# OttoPi09-RPi3A-HAT.net
KiCad netlist of a schematic drawn in EAGLE
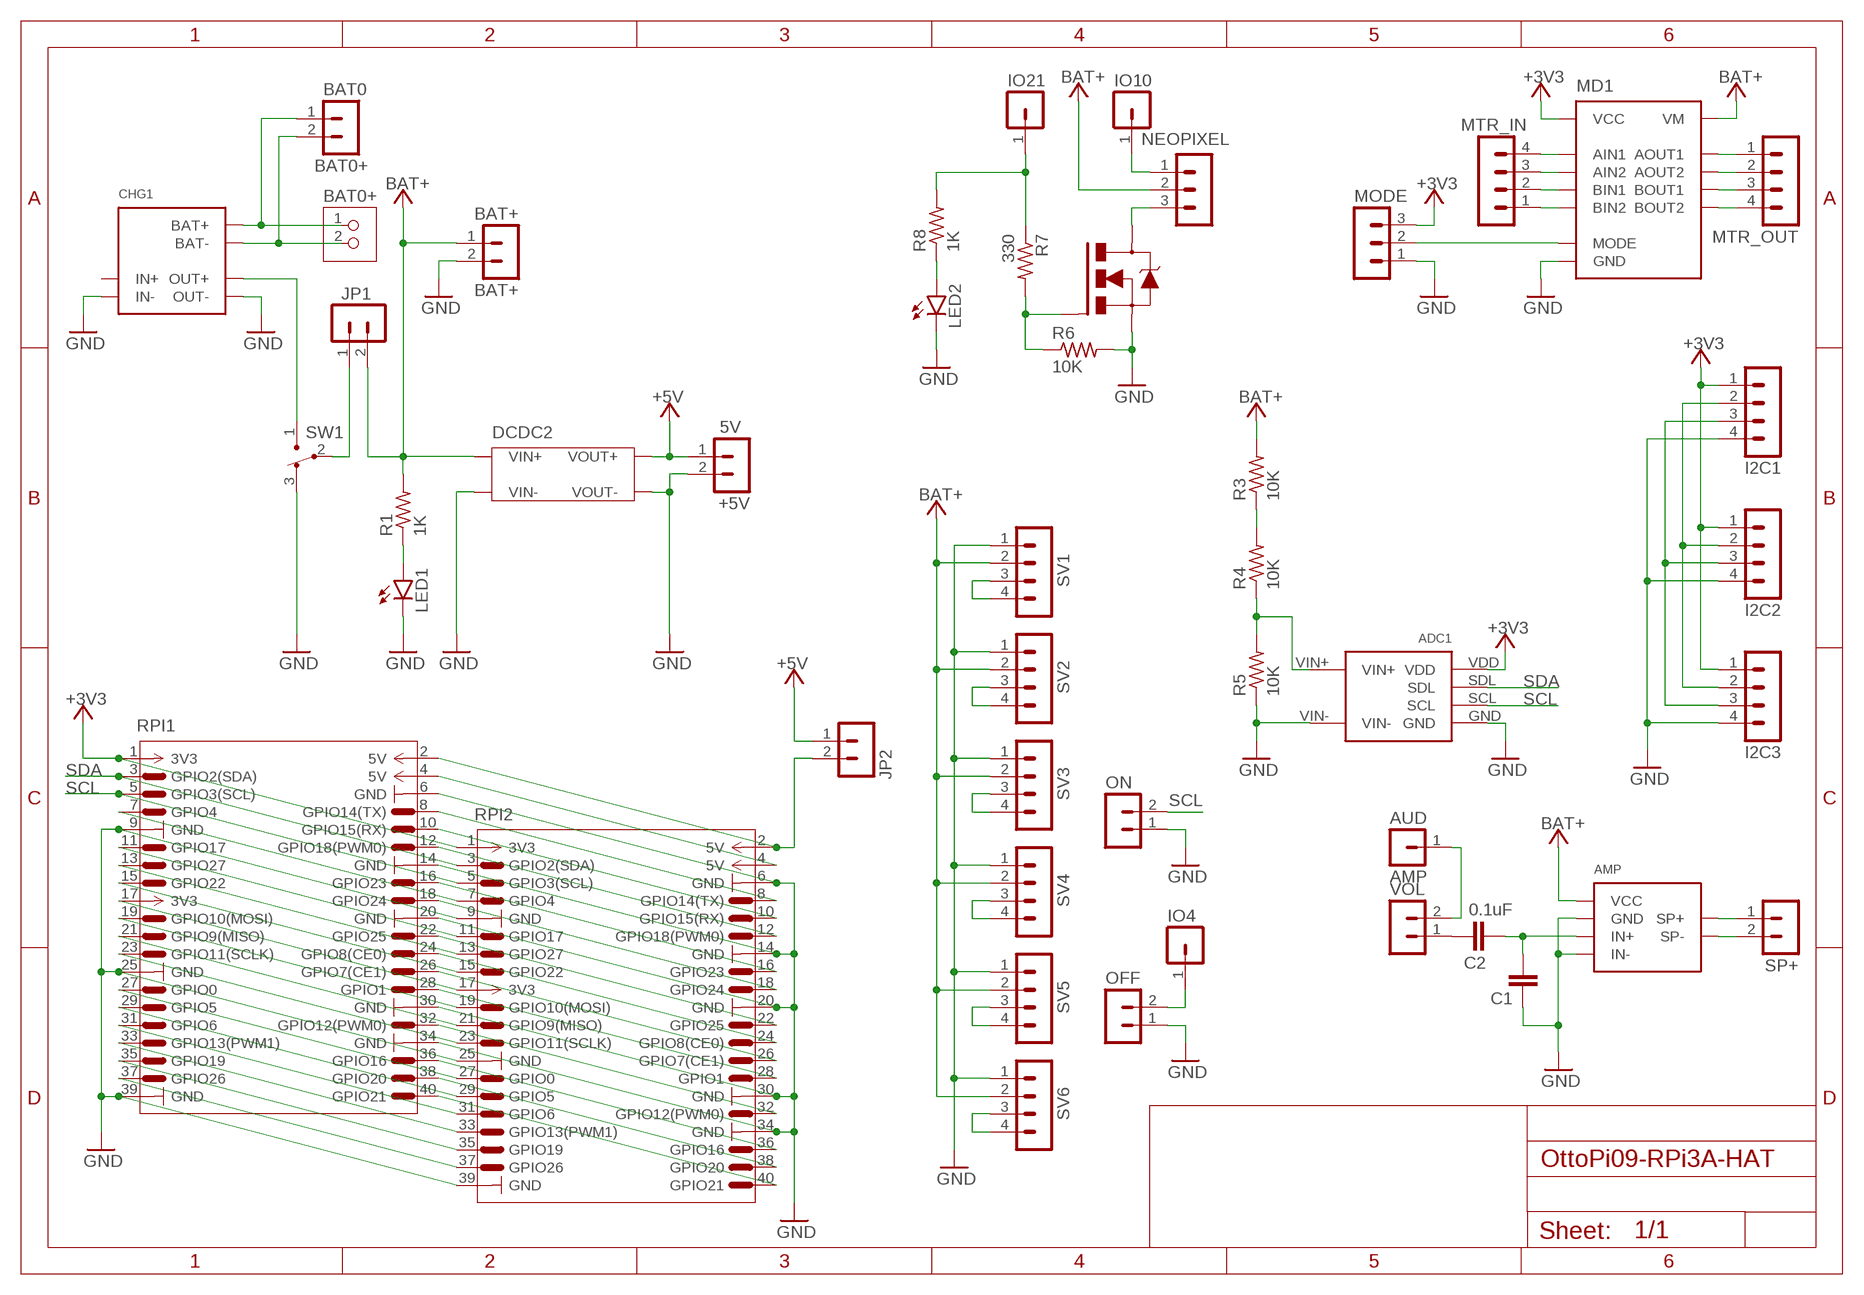
[diagram p0: schematic, sheet 1]

(export (version "E")
  (design (tool "Eeschema 10.0.6"))
  (components
    (comp (ref "+5V")
      (value "5V")
      (footprint "eagle-import:PINHEAD-MA02-1")
      (libsource (lib "eagle-import") (part "PINHEAD-MA02-1"))
    )
    (comp (ref "ADC1")
      (value "MCP3425MOD")
      (footprint "eagle-import:MCP3425MOD")
      (libsource (lib "eagle-import") (part "MCP3425MOD"))
    )
    (comp (ref "AMP")
      (value "AMP")
      (footprint "eagle-import:PAM8012MOD-A")
      (libsource (lib "eagle-import") (part "PAM8012MOD"))
    )
    (comp (ref "AUD")
      (value "AMP")
      (footprint "eagle-import:PINHEAD-MA01-1")
      (libsource (lib "eagle-import") (part "PINHEAD-MA01-1"))
    )
    (comp (ref "BAT+")
      (value "BAT+")
      (footprint "eagle-import:PINHEAD-MA02-1")
      (libsource (lib "eagle-import") (part "PINHEAD-MA02-1"))
    )
    (comp (ref "BAT0")
      (value "BAT0+")
      (footprint "eagle-import:PINHEAD-MA02-1")
      (libsource (lib "eagle-import") (part "PINHEAD-MA02-1"))
    )
    (comp (ref "BAT0+")
      (value "JST-PH2")
      (footprint "eagle-import:JST-PH2")
      (libsource (lib "eagle-import") (part "JST-PH2"))
    )
    (comp (ref "C1")
      (value "C-EU025-024X044")
      (footprint "eagle-import:C025-024X044")
      (libsource (lib "eagle-import") (part "C-EU025-024X044"))
    )
    (comp (ref "C2")
      (value "0.1uF")
      (footprint "eagle-import:C025-024X044")
      (libsource (lib "eagle-import") (part "C-EU025-024X044"))
    )
    (comp (ref "CHG1")
      (value "TP4056MOD1")
      (footprint "eagle-import:TP4056MOD1")
      (libsource (lib "eagle-import") (part "TP4056MOD1"))
    )
    (comp (ref "DCDC2")
      (value "DCDC-SX1308-MOD1")
      (footprint "eagle-import:DCDC-SX1308-MOD1")
      (libsource (lib "eagle-import") (part "DCDC-SX1308-MOD1"))
    )
    (comp (ref "I2C1")
      (value "PINHEAD-MA04-1")
      (footprint "eagle-import:PINHEAD-MA04-1")
      (libsource (lib "eagle-import") (part "PINHEAD-MA04-1"))
    )
    (comp (ref "I2C2")
      (value "PINHEAD-MA04-1")
      (footprint "eagle-import:PINHEAD-MA04-1")
      (libsource (lib "eagle-import") (part "PINHEAD-MA04-1"))
    )
    (comp (ref "I2C3")
      (value "PINHEAD-MA04-1")
      (footprint "eagle-import:PINHEAD-MA04-1")
      (libsource (lib "eagle-import") (part "PINHEAD-MA04-1"))
    )
    (comp (ref "IO4")
      (value "PINHEAD-MA01-1")
      (footprint "eagle-import:PINHEAD-MA01-1")
      (libsource (lib "eagle-import") (part "PINHEAD-MA01-1"))
    )
    (comp (ref "IO10")
      (value "PINHEAD-MA01-1")
      (footprint "eagle-import:PINHEAD-MA01-1")
      (libsource (lib "eagle-import") (part "PINHEAD-MA01-1"))
    )
    (comp (ref "IO21")
      (value "PINHEAD-MA01-1")
      (footprint "eagle-import:PINHEAD-MA01-1")
      (libsource (lib "eagle-import") (part "PINHEAD-MA01-1"))
    )
    (comp (ref "JP1")
      (value "PINHEAD-MA02-1")
      (footprint "eagle-import:PINHEAD-MA02-1")
      (libsource (lib "eagle-import") (part "PINHEAD-MA02-1"))
    )
    (comp (ref "JP2")
      (value "PINHEAD-MA02-1")
      (footprint "eagle-import:PINHEAD-MA02-1")
      (libsource (lib "eagle-import") (part "PINHEAD-MA02-1"))
    )
    (comp (ref "LED1")
      (value "LED3MM")
      (footprint "eagle-import:LED3MM")
      (libsource (lib "eagle-import") (part "LED3MM"))
    )
    (comp (ref "LED2")
      (value "LED3MM")
      (footprint "eagle-import:LED3MM")
      (libsource (lib "eagle-import") (part "LED3MM"))
    )
    (comp (ref "MD1")
      (value "DRV8835MOD")
      (footprint "eagle-import:DRV8835MOD")
      (libsource (lib "eagle-import") (part "DRV8835MOD"))
    )
    (comp (ref "MODE")
      (value "PINHEAD-MA03-1")
      (footprint "eagle-import:PINHEAD-MA03-1")
      (libsource (lib "eagle-import") (part "PINHEAD-MA03-1"))
    )
    (comp (ref "MTR_IN")
      (value "PINHEAD-MA04-1")
      (footprint "eagle-import:PINHEAD-MA04-1")
      (libsource (lib "eagle-import") (part "PINHEAD-MA04-1"))
    )
    (comp (ref "MTR_OUT")
      (value "PINHEAD-MA04-1")
      (footprint "eagle-import:PINHEAD-MA04-1")
      (libsource (lib "eagle-import") (part "PINHEAD-MA04-1"))
    )
    (comp (ref "NEOPIXEL")
      (value "PINHEAD-MA03-1")
      (footprint "eagle-import:PINHEAD-MA03-1")
      (libsource (lib "eagle-import") (part "ytani1_30941153_PINHEAD-MA03-1"))
    )
    (comp (ref "OFF")
      (value "PINHEAD-MA02-1")
      (footprint "eagle-import:PINHEAD-MA02-1")
      (libsource (lib "eagle-import") (part "PINHEAD-MA02-1"))
    )
    (comp (ref "ON")
      (value "PINHEAD-MA02-1")
      (footprint "eagle-import:PINHEAD-MA02-1")
      (libsource (lib "eagle-import") (part "PINHEAD-MA02-1"))
    )
    (comp (ref "Q1")
      (value "2SK4017")
      (footprint "eagle-import:MOSFET-1")
      (libsource (lib "eagle-import") (part "MOSFET-2SK4017"))
    )
    (comp (ref "R1")
      (value "1K")
      (footprint "eagle-import:0204_7")
      (libsource (lib "eagle-import") (part "R-US_0204/7"))
    )
    (comp (ref "R3")
      (value "10K")
      (footprint "eagle-import:0204_7")
      (libsource (lib "eagle-import") (part "R-US_0204/7"))
    )
    (comp (ref "R4")
      (value "10K")
      (footprint "eagle-import:0204_7")
      (libsource (lib "eagle-import") (part "R-US_0204/7"))
    )
    (comp (ref "R5")
      (value "10K")
      (footprint "eagle-import:0204_7")
      (libsource (lib "eagle-import") (part "R-US_0204/7"))
    )
    (comp (ref "R6")
      (value "10K")
      (footprint "eagle-import:0204_7")
      (libsource (lib "eagle-import") (part "R-US_0204/7"))
    )
    (comp (ref "R7")
      (value "330")
      (footprint "eagle-import:0204_7")
      (libsource (lib "eagle-import") (part "R-US_0204/7"))
    )
    (comp (ref "R8")
      (value "1K")
      (footprint "eagle-import:0204_7")
      (libsource (lib "eagle-import") (part "R-US_0204/7"))
    )
    (comp (ref "RPI1")
      (value "RPI-PIN")
      (footprint "eagle-import:RPI-PIN")
      (libsource (lib "eagle-import") (part "RPI-PIN"))
    )
    (comp (ref "RPI2")
      (value "RPI-PIN")
      (footprint "eagle-import:RPI-PIN")
      (libsource (lib "eagle-import") (part "RPI-PIN"))
    )
    (comp (ref "SP+")
      (value "PINHEAD-MA02-1")
      (footprint "eagle-import:PINHEAD-MA02-1")
      (libsource (lib "eagle-import") (part "PINHEAD-MA02-1"))
    )
    (comp (ref "SV1")
      (value "PINHEAD-MA04-1")
      (footprint "eagle-import:PINHEAD-MA04-1")
      (libsource (lib "eagle-import") (part "PINHEAD-MA04-1"))
    )
    (comp (ref "SV2")
      (value "PINHEAD-MA04-1")
      (footprint "eagle-import:PINHEAD-MA04-1")
      (libsource (lib "eagle-import") (part "PINHEAD-MA04-1"))
    )
    (comp (ref "SV3")
      (value "PINHEAD-MA04-1")
      (footprint "eagle-import:PINHEAD-MA04-1")
      (libsource (lib "eagle-import") (part "PINHEAD-MA04-1"))
    )
    (comp (ref "SV4")
      (value "PINHEAD-MA04-1")
      (footprint "eagle-import:PINHEAD-MA04-1")
      (libsource (lib "eagle-import") (part "PINHEAD-MA04-1"))
    )
    (comp (ref "SV5")
      (value "PINHEAD-MA04-1")
      (footprint "eagle-import:PINHEAD-MA04-1")
      (libsource (lib "eagle-import") (part "PINHEAD-MA04-1"))
    )
    (comp (ref "SV6")
      (value "PINHEAD-MA04-1")
      (footprint "eagle-import:PINHEAD-MA04-1")
      (libsource (lib "eagle-import") (part "PINHEAD-MA04-1"))
    )
    (comp (ref "SW1")
      (value "SW3-1")
      (footprint "eagle-import:SW3-1")
      (fields (field (name "MF") "HiLetgo"))
      (libsource (lib "eagle-import") (part "SW3-1"))
    )
    (comp (ref "VOL")
      (value "PINHEAD-MA02-1")
      (footprint "eagle-import:PINHEAD-MA02-1")
      (libsource (lib "eagle-import") (part "PINHEAD-MA02-1"))
    )
  )
  (nets
    (net (code "1") (name "+3V3") (class "Default")
      (node (ref "ADC1") (pin "VDD") (pinfunction "VDD_VDD") (pintype "bidirectional"))
      (node (ref "I2C1") (pin "1") (pinfunction "1_1") (pintype "passive"))
      (node (ref "I2C2") (pin "1") (pinfunction "1_1") (pintype "passive"))
      (node (ref "I2C3") (pin "1") (pinfunction "1_1") (pintype "passive"))
      (node (ref "MD1") (pin "VCC") (pinfunction "VCC_VCC") (pintype "input"))
      (node (ref "MODE") (pin "3") (pinfunction "3_3") (pintype "passive"))
      (node (ref "RPI1") (pin "1") (pinfunction "3V3_1") (pintype "passive"))
      (node (ref "RPI2") (pin "1") (pinfunction "3V3_1") (pintype "passive"))
    )
    (net (code "2") (name "+5V") (class "Default")
      (node (ref "+5V") (pin "1") (pinfunction "1_1") (pintype "passive"))
      (node (ref "DCDC2") (pin "VOUT+") (pinfunction "VOUT+_VOUT+") (pintype "power_in"))
      (node (ref "JP2") (pin "1") (pinfunction "1_1") (pintype "passive"))
    )
    (net (code "3") (name "/SCL") (class "Default")
      (node (ref "ADC1") (pin "SCL") (pinfunction "SCL_SCL") (pintype "bidirectional"))
      (node (ref "I2C1") (pin "3") (pinfunction "3_3") (pintype "passive"))
      (node (ref "I2C2") (pin "3") (pinfunction "3_3") (pintype "passive"))
      (node (ref "I2C3") (pin "3") (pinfunction "3_3") (pintype "passive"))
      (node (ref "ON") (pin "2") (pinfunction "2_2") (pintype "passive"))
      (node (ref "RPI1") (pin "5") (pinfunction "GPIO3(SCL)_5") (pintype "passive"))
      (node (ref "RPI2") (pin "5") (pinfunction "GPIO3(SCL)_5") (pintype "passive"))
    )
    (net (code "4") (name "/SDA") (class "Default")
      (node (ref "ADC1") (pin "SDL") (pinfunction "SDL_SDL") (pintype "bidirectional"))
      (node (ref "I2C1") (pin "2") (pinfunction "2_2") (pintype "passive"))
      (node (ref "I2C2") (pin "2") (pinfunction "2_2") (pintype "passive"))
      (node (ref "I2C3") (pin "2") (pinfunction "2_2") (pintype "passive"))
      (node (ref "RPI1") (pin "3") (pinfunction "GPIO2(SDA)_3") (pintype "passive"))
      (node (ref "RPI2") (pin "3") (pinfunction "GPIO2(SDA)_3") (pintype "passive"))
    )
    (net (code "5") (name "BAT+") (class "Default")
      (node (ref "AMP") (pin "V+") (pinfunction "VCC_V+") (pintype "passive"))
      (node (ref "BAT+") (pin "1") (pinfunction "1_1") (pintype "passive"))
      (node (ref "DCDC2") (pin "VIN+") (pinfunction "VIN+_VIN+") (pintype "power_in"))
      (node (ref "JP1") (pin "2") (pinfunction "2_2") (pintype "passive"))
      (node (ref "MD1") (pin "VM") (pinfunction "VM_VM") (pintype "input"))
      (node (ref "NEOPIXEL") (pin "2") (pinfunction "2_2") (pintype "passive"))
      (node (ref "R1") (pin "2") (pinfunction "2_2") (pintype "passive"))
      (node (ref "R3") (pin "2") (pinfunction "2_2") (pintype "passive"))
      (node (ref "SV1") (pin "2") (pinfunction "2_2") (pintype "passive"))
      (node (ref "SV2") (pin "2") (pinfunction "2_2") (pintype "passive"))
      (node (ref "SV3") (pin "2") (pinfunction "2_2") (pintype "passive"))
      (node (ref "SV4") (pin "2") (pinfunction "2_2") (pintype "passive"))
      (node (ref "SV5") (pin "2") (pinfunction "2_2") (pintype "passive"))
      (node (ref "SV6") (pin "2") (pinfunction "2_2") (pintype "passive"))
    )
    (net (code "6") (name "GND") (class "Default")
      (node (ref "+5V") (pin "2") (pinfunction "2_2") (pintype "passive"))
      (node (ref "ADC1") (pin "GND") (pinfunction "GND_GND") (pintype "bidirectional"))
      (node (ref "ADC1") (pin "VIN-") (pinfunction "VIN-_VIN-") (pintype "bidirectional"))
      (node (ref "AMP") (pin "GND") (pinfunction "GND_GND") (pintype "passive"))
      (node (ref "AMP") (pin "IN-") (pinfunction "IN-_IN-") (pintype "input"))
      (node (ref "BAT+") (pin "2") (pinfunction "2_2") (pintype "passive"))
      (node (ref "C1") (pin "1") (pinfunction "1_1") (pintype "passive"))
      (node (ref "CHG1") (pin "IN-") (pinfunction "IN-_IN-") (pintype "passive"))
      (node (ref "CHG1") (pin "OUT-") (pinfunction "OUT-_OUT-") (pintype "passive"))
      (node (ref "DCDC2") (pin "VIN-") (pinfunction "VIN-_VIN-") (pintype "power_in"))
      (node (ref "DCDC2") (pin "VOUT-") (pinfunction "VOUT-_VOUT-") (pintype "power_in"))
      (node (ref "I2C1") (pin "4") (pinfunction "4_4") (pintype "passive"))
      (node (ref "I2C2") (pin "4") (pinfunction "4_4") (pintype "passive"))
      (node (ref "I2C3") (pin "4") (pinfunction "4_4") (pintype "passive"))
      (node (ref "LED1") (pin "K") (pinfunction "C_K") (pintype "passive"))
      (node (ref "LED2") (pin "K") (pinfunction "C_K") (pintype "passive"))
      (node (ref "MD1") (pin "GND") (pinfunction "GND_GND") (pintype "power_in"))
      (node (ref "MODE") (pin "1") (pinfunction "1_1") (pintype "passive"))
      (node (ref "OFF") (pin "1") (pinfunction "1_1") (pintype "passive"))
      (node (ref "ON") (pin "1") (pinfunction "1_1") (pintype "passive"))
      (node (ref "Q1") (pin "S") (pinfunction "S_S") (pintype "bidirectional"))
      (node (ref "R5") (pin "1") (pinfunction "1_1") (pintype "passive"))
      (node (ref "R6") (pin "2") (pinfunction "2_2") (pintype "passive"))
      (node (ref "RPI1") (pin "14") (pinfunction "GND_14") (pintype "passive"))
      (node (ref "RPI1") (pin "20") (pinfunction "GND_20") (pintype "passive"))
      (node (ref "RPI1") (pin "25") (pinfunction "GND_25") (pintype "passive"))
      (node (ref "RPI1") (pin "30") (pinfunction "GND_30") (pintype "passive"))
      (node (ref "RPI1") (pin "34") (pinfunction "GND_34") (pintype "passive"))
      (node (ref "RPI1") (pin "39") (pinfunction "GND_39") (pintype "passive"))
      (node (ref "RPI1") (pin "6") (pinfunction "GND_6") (pintype "passive"))
      (node (ref "RPI1") (pin "9") (pinfunction "GND_9") (pintype "passive"))
      (node (ref "RPI2") (pin "14") (pinfunction "GND_14") (pintype "passive"))
      (node (ref "RPI2") (pin "20") (pinfunction "GND_20") (pintype "passive"))
      (node (ref "RPI2") (pin "25") (pinfunction "GND_25") (pintype "passive"))
      (node (ref "RPI2") (pin "30") (pinfunction "GND_30") (pintype "passive"))
      (node (ref "RPI2") (pin "34") (pinfunction "GND_34") (pintype "passive"))
      (node (ref "RPI2") (pin "39") (pinfunction "GND_39") (pintype "passive"))
      (node (ref "RPI2") (pin "6") (pinfunction "GND_6") (pintype "passive"))
      (node (ref "RPI2") (pin "9") (pinfunction "GND_9") (pintype "passive"))
      (node (ref "SV1") (pin "1") (pinfunction "1_1") (pintype "passive"))
      (node (ref "SV2") (pin "1") (pinfunction "1_1") (pintype "passive"))
      (node (ref "SV3") (pin "1") (pinfunction "1_1") (pintype "passive"))
      (node (ref "SV4") (pin "1") (pinfunction "1_1") (pintype "passive"))
      (node (ref "SV5") (pin "1") (pinfunction "1_1") (pintype "passive"))
      (node (ref "SV6") (pin "1") (pinfunction "1_1") (pintype "passive"))
      (node (ref "SW1") (pin "3") (pinfunction "3_3") (pintype "passive"))
    )
    (net (code "7") (name "Net-(ADC1-PadVIN+)") (class "Default")
      (node (ref "ADC1") (pin "VIN+") (pinfunction "VIN+_VIN+") (pintype "bidirectional"))
      (node (ref "R4") (pin "1") (pinfunction "1_1") (pintype "passive"))
      (node (ref "R5") (pin "2") (pinfunction "2_2") (pintype "passive"))
    )
    (net (code "8") (name "Net-(AMP-PadIN+)") (class "Default")
      (node (ref "AMP") (pin "IN+") (pinfunction "IN+_IN+") (pintype "input"))
      (node (ref "C1") (pin "2") (pinfunction "2_2") (pintype "passive"))
      (node (ref "C2") (pin "1") (pinfunction "1_1") (pintype "passive"))
    )
    (net (code "9") (name "Net-(AMP-SP+)") (class "Default")
      (node (ref "AMP") (pin "SP+@1") (pinfunction "SP+_SP+@1") (pintype "output"))
      (node (ref "SP+") (pin "1") (pinfunction "1_1") (pintype "passive"))
    )
    (net (code "10") (name "Net-(AMP-SP-)") (class "Default")
      (node (ref "AMP") (pin "SP-@1") (pinfunction "SP-_SP-@1") (pintype "output"))
      (node (ref "SP+") (pin "2") (pinfunction "2_2") (pintype "passive"))
    )
    (net (code "11") (name "Net-(AUD-Pad1)") (class "Default")
      (node (ref "AUD") (pin "1") (pinfunction "1_1") (pintype "passive"))
      (node (ref "VOL") (pin "2") (pinfunction "2_2") (pintype "passive"))
    )
    (net (code "12") (name "Net-(BAT0+-Pad1)") (class "Default")
      (node (ref "BAT0") (pin "1") (pinfunction "1_1") (pintype "passive"))
      (node (ref "BAT0+") (pin "1") (pinfunction "1_1") (pintype "passive"))
      (node (ref "CHG1") (pin "BAT+") (pinfunction "BAT+_BAT+") (pintype "passive"))
    )
    (net (code "13") (name "Net-(BAT0+-Pad2)") (class "Default")
      (node (ref "BAT0") (pin "2") (pinfunction "2_2") (pintype "passive"))
      (node (ref "BAT0+") (pin "2") (pinfunction "2_2") (pintype "passive"))
      (node (ref "CHG1") (pin "BAT-") (pinfunction "BAT-_BAT-") (pintype "passive"))
    )
    (net (code "14") (name "Net-(C2-Pad2)") (class "Default")
      (node (ref "C2") (pin "2") (pinfunction "2_2") (pintype "passive"))
      (node (ref "VOL") (pin "1") (pinfunction "1_1") (pintype "passive"))
    )
    (net (code "15") (name "Net-(CHG1-PadOUT+)") (class "Default")
      (node (ref "CHG1") (pin "OUT+") (pinfunction "OUT+_OUT+") (pintype "passive"))
      (node (ref "SW1") (pin "1") (pinfunction "1_1") (pintype "passive"))
    )
    (net (code "16") (name "Net-(IO4-Pad1)") (class "Default")
      (node (ref "IO4") (pin "1") (pinfunction "1_1") (pintype "passive"))
      (node (ref "OFF") (pin "2") (pinfunction "2_2") (pintype "passive"))
    )
    (net (code "17") (name "Net-(IO10-Pad1)") (class "Default")
      (node (ref "IO10") (pin "1") (pinfunction "1_1") (pintype "passive"))
      (node (ref "NEOPIXEL") (pin "1") (pinfunction "1_1") (pintype "passive"))
    )
    (net (code "18") (name "Net-(IO21-Pad1)") (class "Default")
      (node (ref "IO21") (pin "1") (pinfunction "1_1") (pintype "passive"))
      (node (ref "R7") (pin "1") (pinfunction "1_1") (pintype "passive"))
      (node (ref "R8") (pin "2") (pinfunction "2_2") (pintype "passive"))
    )
    (net (code "19") (name "Net-(JP1-Pad1)") (class "Default")
      (node (ref "JP1") (pin "1") (pinfunction "1_1") (pintype "passive"))
      (node (ref "SW1") (pin "2") (pinfunction "2_2") (pintype "passive"))
    )
    (net (code "20") (name "Net-(JP2-Pad2)") (class "Default")
      (node (ref "JP2") (pin "2") (pinfunction "2_2") (pintype "passive"))
      (node (ref "RPI1") (pin "2") (pinfunction "5V_2") (pintype "passive"))
      (node (ref "RPI2") (pin "2") (pinfunction "5V_2") (pintype "passive"))
    )
    (net (code "21") (name "Net-(LED1-PadA)") (class "Default")
      (node (ref "LED1") (pin "A") (pinfunction "A_A") (pintype "passive"))
      (node (ref "R1") (pin "1") (pinfunction "1_1") (pintype "passive"))
    )
    (net (code "22") (name "Net-(LED2-PadA)") (class "Default")
      (node (ref "LED2") (pin "A") (pinfunction "A_A") (pintype "passive"))
      (node (ref "R8") (pin "1") (pinfunction "1_1") (pintype "passive"))
    )
    (net (code "23") (name "Net-(MD1-PadAIN1)") (class "Default")
      (node (ref "MD1") (pin "AIN1") (pinfunction "AIN1_AIN1") (pintype "input"))
      (node (ref "MTR_IN") (pin "4") (pinfunction "4_4") (pintype "passive"))
    )
    (net (code "24") (name "Net-(MD1-PadAIN2)") (class "Default")
      (node (ref "MD1") (pin "AIN2") (pinfunction "AIN2_AIN2") (pintype "input"))
      (node (ref "MTR_IN") (pin "3") (pinfunction "3_3") (pintype "passive"))
    )
    (net (code "25") (name "Net-(MD1-PadAOUT1)") (class "Default")
      (node (ref "MD1") (pin "AOUT1") (pinfunction "AOUT1_AOUT1") (pintype "output"))
      (node (ref "MTR_OUT") (pin "1") (pinfunction "1_1") (pintype "passive"))
    )
    (net (code "26") (name "Net-(MD1-PadAOUT2)") (class "Default")
      (node (ref "MD1") (pin "AOUT2") (pinfunction "AOUT2_AOUT2") (pintype "output"))
      (node (ref "MTR_OUT") (pin "2") (pinfunction "2_2") (pintype "passive"))
    )
    (net (code "27") (name "Net-(MD1-PadBIN1)") (class "Default")
      (node (ref "MD1") (pin "BIN1") (pinfunction "BIN1_BIN1") (pintype "input"))
      (node (ref "MTR_IN") (pin "2") (pinfunction "2_2") (pintype "passive"))
    )
    (net (code "28") (name "Net-(MD1-PadBIN2)") (class "Default")
      (node (ref "MD1") (pin "BIN2") (pinfunction "BIN2_BIN2") (pintype "input"))
      (node (ref "MTR_IN") (pin "1") (pinfunction "1_1") (pintype "passive"))
    )
    (net (code "29") (name "Net-(MD1-PadBOUT1)") (class "Default")
      (node (ref "MD1") (pin "BOUT1") (pinfunction "BOUT1_BOUT1") (pintype "output"))
      (node (ref "MTR_OUT") (pin "3") (pinfunction "3_3") (pintype "passive"))
    )
    (net (code "30") (name "Net-(MD1-PadBOUT2)") (class "Default")
      (node (ref "MD1") (pin "BOUT2") (pinfunction "BOUT2_BOUT2") (pintype "output"))
      (node (ref "MTR_OUT") (pin "4") (pinfunction "4_4") (pintype "passive"))
    )
    (net (code "31") (name "Net-(MD1-PadMODE)") (class "Default")
      (node (ref "MD1") (pin "MODE") (pinfunction "MODE_MODE") (pintype "input"))
      (node (ref "MODE") (pin "2") (pinfunction "2_2") (pintype "passive"))
    )
    (net (code "32") (name "Net-(NEOPIXEL-Pad3)") (class "Default")
      (node (ref "NEOPIXEL") (pin "3") (pinfunction "3_3") (pintype "passive"))
      (node (ref "Q1") (pin "D") (pinfunction "D_D") (pintype "bidirectional"))
    )
    (net (code "33") (name "Net-(Q1-PadG)") (class "Default")
      (node (ref "Q1") (pin "G") (pinfunction "G_G") (pintype "bidirectional"))
      (node (ref "R6") (pin "1") (pinfunction "1_1") (pintype "passive"))
      (node (ref "R7") (pin "2") (pinfunction "2_2") (pintype "passive"))
    )
    (net (code "34") (name "Net-(R3-Pad1)") (class "Default")
      (node (ref "R3") (pin "1") (pinfunction "1_1") (pintype "passive"))
      (node (ref "R4") (pin "2") (pinfunction "2_2") (pintype "passive"))
    )
    (net (code "35") (name "Net-(RPI1-3V3-Pad17)") (class "Default")
      (node (ref "RPI1") (pin "17") (pinfunction "3V3_17") (pintype "passive"))
      (node (ref "RPI2") (pin "17") (pinfunction "3V3_17") (pintype "passive"))
    )
    (net (code "36") (name "Net-(RPI1-5V-Pad4)") (class "Default")
      (node (ref "RPI1") (pin "4") (pinfunction "5V_4") (pintype "passive"))
      (node (ref "RPI2") (pin "4") (pinfunction "5V_4") (pintype "passive"))
    )
    (net (code "37") (name "Net-(RPI1-GPIO0)") (class "Default")
      (node (ref "RPI1") (pin "27") (pinfunction "GPIO0_27") (pintype "passive"))
      (node (ref "RPI2") (pin "27") (pinfunction "GPIO0_27") (pintype "passive"))
    )
    (net (code "38") (name "Net-(RPI1-GPIO1)") (class "Default")
      (node (ref "RPI1") (pin "28") (pinfunction "GPIO1_28") (pintype "passive"))
      (node (ref "RPI2") (pin "28") (pinfunction "GPIO1_28") (pintype "passive"))
    )
    (net (code "39") (name "Net-(RPI1-GPIO4)") (class "Default")
      (node (ref "RPI1") (pin "7") (pinfunction "GPIO4_7") (pintype "passive"))
      (node (ref "RPI2") (pin "7") (pinfunction "GPIO4_7") (pintype "passive"))
    )
    (net (code "40") (name "Net-(RPI1-GPIO5)") (class "Default")
      (node (ref "RPI1") (pin "29") (pinfunction "GPIO5_29") (pintype "passive"))
      (node (ref "RPI2") (pin "29") (pinfunction "GPIO5_29") (pintype "passive"))
    )
    (net (code "41") (name "Net-(RPI1-GPIO6)") (class "Default")
      (node (ref "RPI1") (pin "31") (pinfunction "GPIO6_31") (pintype "passive"))
      (node (ref "RPI2") (pin "31") (pinfunction "GPIO6_31") (pintype "passive"))
    )
    (net (code "42") (name "Net-(RPI1-GPIO7(CE1))") (class "Default")
      (node (ref "RPI1") (pin "26") (pinfunction "GPIO7(CE1)_26") (pintype "passive"))
      (node (ref "RPI2") (pin "26") (pinfunction "GPIO7(CE1)_26") (pintype "passive"))
    )
    (net (code "43") (name "Net-(RPI1-GPIO8(CE0))") (class "Default")
      (node (ref "RPI1") (pin "24") (pinfunction "GPIO8(CE0)_24") (pintype "passive"))
      (node (ref "RPI2") (pin "24") (pinfunction "GPIO8(CE0)_24") (pintype "passive"))
    )
    (net (code "44") (name "Net-(RPI1-GPIO9(MISO))") (class "Default")
      (node (ref "RPI1") (pin "21") (pinfunction "GPIO9(MISO)_21") (pintype "passive"))
      (node (ref "RPI2") (pin "21") (pinfunction "GPIO9(MISO)_21") (pintype "passive"))
    )
    (net (code "45") (name "Net-(RPI1-GPIO10(MOSI))") (class "Default")
      (node (ref "RPI1") (pin "19") (pinfunction "GPIO10(MOSI)_19") (pintype "passive"))
      (node (ref "RPI2") (pin "19") (pinfunction "GPIO10(MOSI)_19") (pintype "passive"))
    )
    (net (code "46") (name "Net-(RPI1-GPIO11(SCLK))") (class "Default")
      (node (ref "RPI1") (pin "23") (pinfunction "GPIO11(SCLK)_23") (pintype "passive"))
      (node (ref "RPI2") (pin "23") (pinfunction "GPIO11(SCLK)_23") (pintype "passive"))
    )
    (net (code "47") (name "Net-(RPI1-GPIO12(PWM0))") (class "Default")
      (node (ref "RPI1") (pin "32") (pinfunction "GPIO12(PWM0)_32") (pintype "passive"))
      (node (ref "RPI2") (pin "32") (pinfunction "GPIO12(PWM0)_32") (pintype "passive"))
    )
    (net (code "48") (name "Net-(RPI1-GPIO13(PWM1))") (class "Default")
      (node (ref "RPI1") (pin "33") (pinfunction "GPIO13(PWM1)_33") (pintype "passive"))
      (node (ref "RPI2") (pin "33") (pinfunction "GPIO13(PWM1)_33") (pintype "passive"))
    )
    (net (code "49") (name "Net-(RPI1-GPIO14(TX))") (class "Default")
      (node (ref "RPI1") (pin "8") (pinfunction "GPIO14(TX)_8") (pintype "passive"))
      (node (ref "RPI2") (pin "8") (pinfunction "GPIO14(TX)_8") (pintype "passive"))
    )
    (net (code "50") (name "Net-(RPI1-GPIO15(RX))") (class "Default")
      (node (ref "RPI1") (pin "10") (pinfunction "GPIO15(RX)_10") (pintype "passive"))
      (node (ref "RPI2") (pin "10") (pinfunction "GPIO15(RX)_10") (pintype "passive"))
    )
    (net (code "51") (name "Net-(RPI1-GPIO16)") (class "Default")
      (node (ref "RPI1") (pin "36") (pinfunction "GPIO16_36") (pintype "passive"))
      (node (ref "RPI2") (pin "36") (pinfunction "GPIO16_36") (pintype "passive"))
    )
    (net (code "52") (name "Net-(RPI1-GPIO17)") (class "Default")
      (node (ref "RPI1") (pin "11") (pinfunction "GPIO17_11") (pintype "passive"))
      (node (ref "RPI2") (pin "11") (pinfunction "GPIO17_11") (pintype "passive"))
    )
    (net (code "53") (name "Net-(RPI1-GPIO18(PWM0))") (class "Default")
      (node (ref "RPI1") (pin "12") (pinfunction "GPIO18(PWM0)_12") (pintype "passive"))
      (node (ref "RPI2") (pin "12") (pinfunction "GPIO18(PWM0)_12") (pintype "passive"))
    )
    (net (code "54") (name "Net-(RPI1-GPIO19)") (class "Default")
      (node (ref "RPI1") (pin "35") (pinfunction "GPIO19_35") (pintype "passive"))
      (node (ref "RPI2") (pin "35") (pinfunction "GPIO19_35") (pintype "passive"))
    )
    (net (code "55") (name "Net-(RPI1-GPIO20)") (class "Default")
      (node (ref "RPI1") (pin "38") (pinfunction "GPIO20_38") (pintype "passive"))
      (node (ref "RPI2") (pin "38") (pinfunction "GPIO20_38") (pintype "passive"))
    )
    (net (code "56") (name "Net-(RPI1-GPIO21)") (class "Default")
      (node (ref "RPI1") (pin "40") (pinfunction "GPIO21_40") (pintype "passive"))
      (node (ref "RPI2") (pin "40") (pinfunction "GPIO21_40") (pintype "passive"))
    )
    (net (code "57") (name "Net-(RPI1-GPIO22)") (class "Default")
      (node (ref "RPI1") (pin "15") (pinfunction "GPIO22_15") (pintype "passive"))
      (node (ref "RPI2") (pin "15") (pinfunction "GPIO22_15") (pintype "passive"))
    )
    (net (code "58") (name "Net-(RPI1-GPIO23)") (class "Default")
      (node (ref "RPI1") (pin "16") (pinfunction "GPIO23_16") (pintype "passive"))
      (node (ref "RPI2") (pin "16") (pinfunction "GPIO23_16") (pintype "passive"))
    )
    (net (code "59") (name "Net-(RPI1-GPIO24)") (class "Default")
      (node (ref "RPI1") (pin "18") (pinfunction "GPIO24_18") (pintype "passive"))
      (node (ref "RPI2") (pin "18") (pinfunction "GPIO24_18") (pintype "passive"))
    )
    (net (code "60") (name "Net-(RPI1-GPIO25)") (class "Default")
      (node (ref "RPI1") (pin "22") (pinfunction "GPIO25_22") (pintype "passive"))
      (node (ref "RPI2") (pin "22") (pinfunction "GPIO25_22") (pintype "passive"))
    )
    (net (code "61") (name "Net-(RPI1-GPIO26)") (class "Default")
      (node (ref "RPI1") (pin "37") (pinfunction "GPIO26_37") (pintype "passive"))
      (node (ref "RPI2") (pin "37") (pinfunction "GPIO26_37") (pintype "passive"))
    )
    (net (code "62") (name "Net-(RPI1-GPIO27)") (class "Default")
      (node (ref "RPI1") (pin "13") (pinfunction "GPIO27_13") (pintype "passive"))
      (node (ref "RPI2") (pin "13") (pinfunction "GPIO27_13") (pintype "passive"))
    )
    (net (code "63") (name "Net-(SV1-Pad3)") (class "Default")
      (node (ref "SV1") (pin "3") (pinfunction "3_3") (pintype "passive"))
      (node (ref "SV1") (pin "4") (pinfunction "4_4") (pintype "passive"))
    )
    (net (code "64") (name "Net-(SV2-Pad3)") (class "Default")
      (node (ref "SV2") (pin "3") (pinfunction "3_3") (pintype "passive"))
      (node (ref "SV2") (pin "4") (pinfunction "4_4") (pintype "passive"))
    )
    (net (code "65") (name "Net-(SV3-Pad3)") (class "Default")
      (node (ref "SV3") (pin "3") (pinfunction "3_3") (pintype "passive"))
      (node (ref "SV3") (pin "4") (pinfunction "4_4") (pintype "passive"))
    )
    (net (code "66") (name "Net-(SV4-Pad3)") (class "Default")
      (node (ref "SV4") (pin "3") (pinfunction "3_3") (pintype "passive"))
      (node (ref "SV4") (pin "4") (pinfunction "4_4") (pintype "passive"))
    )
    (net (code "67") (name "Net-(SV5-Pad3)") (class "Default")
      (node (ref "SV5") (pin "3") (pinfunction "3_3") (pintype "passive"))
      (node (ref "SV5") (pin "4") (pinfunction "4_4") (pintype "passive"))
    )
    (net (code "68") (name "Net-(SV6-Pad3)") (class "Default")
      (node (ref "SV6") (pin "3") (pinfunction "3_3") (pintype "passive"))
      (node (ref "SV6") (pin "4") (pinfunction "4_4") (pintype "passive"))
    )
    (net (code "69") (name "unconnected-(CHG1-PadIN+)") (class "Default")
      (node (ref "CHG1") (pin "IN+") (pinfunction "IN+_IN+") (pintype "passive"))
    )
  )
)
